# OpenROV_Topside_Interface_2_6.net
KiCad netlist of a schematic drawn in EAGLE
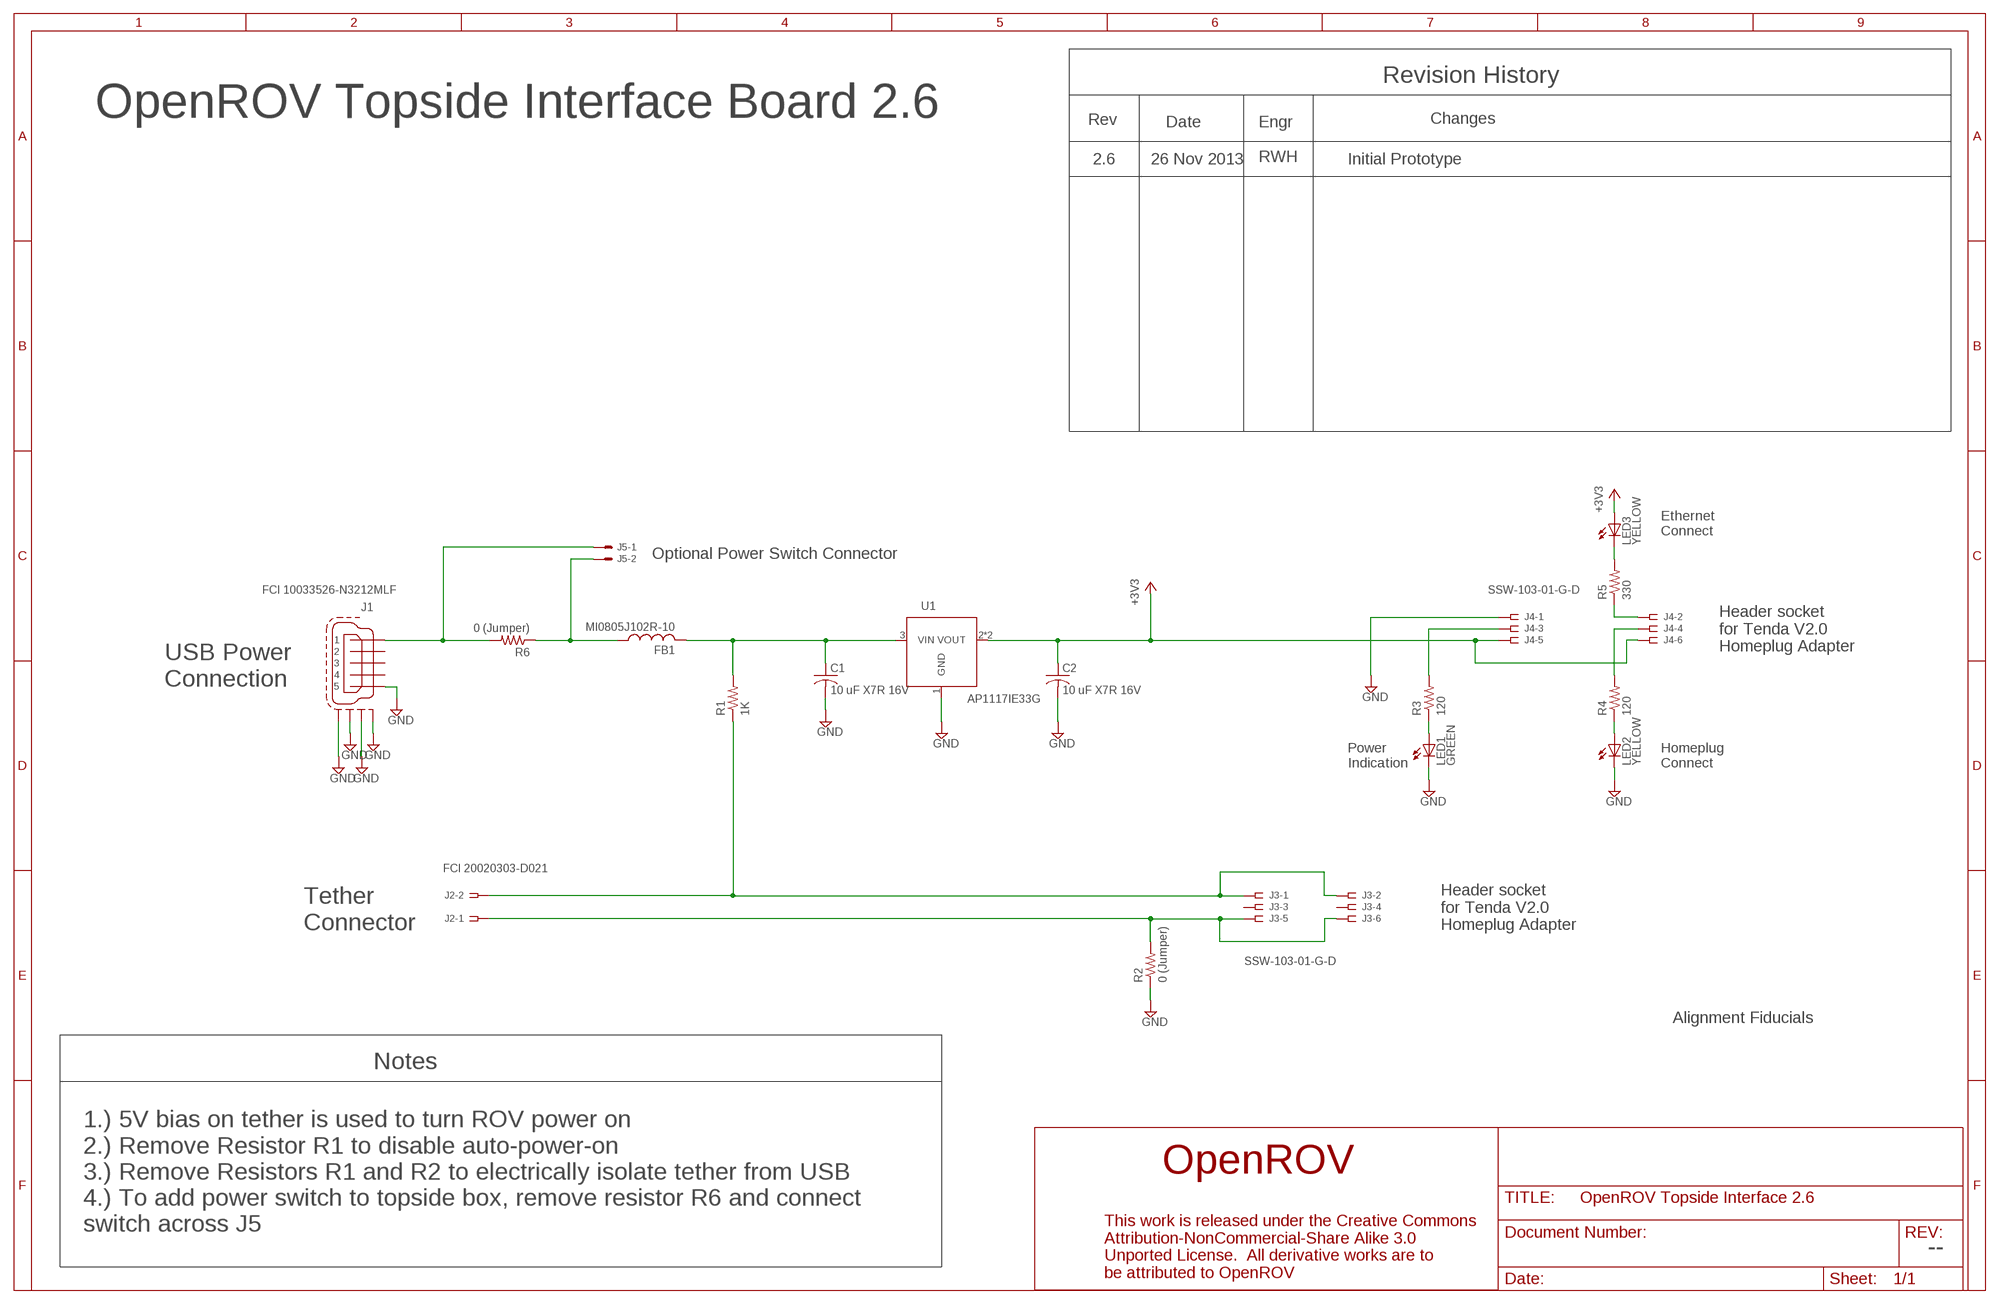
[diagram p0: schematic, sheet 1]

(export (version "E")
  (design (tool "Eeschema 10.0.6"))
  (components
    (comp (ref "C1")
      (value "10 uF X7R 16V")
      (footprint "eagle-import:R1206")
      (libsource (lib "eagle-import") (part "CAP1206"))
    )
    (comp (ref "C2")
      (value "10 uF X7R 16V")
      (footprint "eagle-import:R1206")
      (libsource (lib "eagle-import") (part "CAP1206"))
    )
    (comp (ref "FB1")
      (value "MI0805J102R-10")
      (footprint "eagle-import:R0805")
      (libsource (lib "eagle-import") (part "FERRITESIZE_0805"))
    )
    (comp (ref "J1")
      (value "FCI 10033526-N3212MLF")
      (footprint "eagle-import:USB_MINI-B_SM")
      (libsource (lib "eagle-import") (part "USB_MINI-BSURFACE_MOUNT"))
    )
    (comp (ref "J2")
      (value "FCI 20020303-D021")
      (footprint "eagle-import:FCI_09-381_2PL")
      (libsource (lib "eagle-import") (part "FCI_TERMINAL_BLOCK_2PL"))
    )
    (comp (ref "J3")
      (value "SSW-103-01-G-D")
      (footprint "eagle-import:SSW-103-02-S-D")
      (fields (field (name "MPN") "SSW-103-02-S-D"))
      (libsource (lib "eagle-import") (part "HDR_SOCKET_2X3"))
    )
    (comp (ref "J4")
      (value "SSW-103-01-G-D")
      (footprint "eagle-import:SSW-103-02-S-D")
      (fields (field (name "MPN") "SSW-103-02-S-D"))
      (libsource (lib "eagle-import") (part "HDR_SOCKET_2X3"))
    )
    (comp (ref "J5")
      (value "HDR_1X2X0.100-ALT_SILK")
      (footprint "eagle-import:22-23-2021_ALT_SILK")
      (libsource (lib "eagle-import") (part "HDR_1X2X0.100-ALT_SILK"))
    )
    (comp (ref "LED1")
      (value "GREEN")
      (footprint "eagle-import:LED_0805_BOTTOM_MT(OSRAM)")
      (libsource (lib "eagle-import") (part "LED-0805_BOTTOM_MT"))
    )
    (comp (ref "LED2")
      (value "YELLOW")
      (footprint "eagle-import:LED_0805_BOTTOM_MT(OSRAM)")
      (libsource (lib "eagle-import") (part "LED-0805_BOTTOM_MT"))
    )
    (comp (ref "LED3")
      (value "YELLOW")
      (footprint "eagle-import:LED_0805_BOTTOM_MT(OSRAM)")
      (libsource (lib "eagle-import") (part "LED-0805_BOTTOM_MT"))
    )
    (comp (ref "R1")
      (value "1K")
      (footprint "eagle-import:R0805")
      (libsource (lib "eagle-import") (part "RESISTOR-0805"))
    )
    (comp (ref "R2")
      (value "0 (Jumper)")
      (footprint "eagle-import:R0805")
      (libsource (lib "eagle-import") (part "RESISTOR-0805"))
    )
    (comp (ref "R3")
      (value "120")
      (footprint "eagle-import:R0805")
      (libsource (lib "eagle-import") (part "RESISTOR-0805"))
    )
    (comp (ref "R4")
      (value "120")
      (footprint "eagle-import:R0805")
      (libsource (lib "eagle-import") (part "RESISTOR-0805"))
    )
    (comp (ref "R5")
      (value "330")
      (footprint "eagle-import:R0805")
      (libsource (lib "eagle-import") (part "RESISTOR-0805"))
    )
    (comp (ref "R6")
      (value "0 (Jumper)")
      (footprint "eagle-import:R0805")
      (libsource (lib "eagle-import") (part "RESISTOR-0805"))
    )
    (comp (ref "U1")
      (value "AP1117IE33G")
      (footprint "eagle-import:SOT223")
      (libsource (lib "eagle-import") (part "AP1117SOT223"))
    )
  )
  (nets
    (net (code "1") (name "+3V3") (class "Default")
      (node (ref "C2") (pin "1") (pinfunction "1_1") (pintype "passive"))
      (node (ref "J4") (pin "5") (pinfunction "1_5") (pintype "passive"))
      (node (ref "J4") (pin "6") (pinfunction "1_6") (pintype "passive"))
      (node (ref "LED3") (pin "A") (pinfunction "A_A") (pintype "passive"))
      (node (ref "U1") (pin "2") (pinfunction "VOUT_2") (pintype "bidirectional"))
      (node (ref "U1") (pin "4") (pinfunction "VOUT_4") (pintype "bidirectional"))
    )
    (net (code "2") (name "GND") (class "Default")
      (node (ref "C1") (pin "2") (pinfunction "2_2") (pintype "passive"))
      (node (ref "C2") (pin "2") (pinfunction "2_2") (pintype "passive"))
      (node (ref "J1") (pin "5") (pinfunction "5_5") (pintype "passive"))
      (node (ref "J1") (pin "M1") (pinfunction "S1_M1") (pintype "passive"))
      (node (ref "J1") (pin "M2") (pinfunction "S2_M2") (pintype "passive"))
      (node (ref "J1") (pin "M3") (pinfunction "S3_M3") (pintype "passive"))
      (node (ref "J1") (pin "M4") (pinfunction "S4_M4") (pintype "passive"))
      (node (ref "J4") (pin "1") (pinfunction "1_1") (pintype "passive"))
      (node (ref "LED1") (pin "C") (pinfunction "C_C") (pintype "passive"))
      (node (ref "LED2") (pin "C") (pinfunction "C_C") (pintype "passive"))
      (node (ref "R2") (pin "1") (pinfunction "1_1") (pintype "passive"))
      (node (ref "U1") (pin "1") (pinfunction "GND_1") (pintype "power_in"))
    )
    (net (code "3") (name "Net-(J3B-1)") (class "Default")
      (node (ref "J2") (pin "2A") (pinfunction "1_2A") (pintype "passive"))
      (node (ref "J2") (pin "2B") (pinfunction "1_2B") (pintype "passive"))
      (node (ref "J3") (pin "1") (pinfunction "1_1") (pintype "passive"))
      (node (ref "J3") (pin "2") (pinfunction "1_2") (pintype "passive"))
      (node (ref "R1") (pin "1") (pinfunction "1_1") (pintype "passive"))
    )
    (net (code "4") (name "Net-(J3E-1)") (class "Default")
      (node (ref "J2") (pin "1A") (pinfunction "1_1A") (pintype "passive"))
      (node (ref "J2") (pin "1B") (pinfunction "1_1B") (pintype "passive"))
      (node (ref "J3") (pin "5") (pinfunction "1_5") (pintype "passive"))
      (node (ref "J3") (pin "6") (pinfunction "1_6") (pintype "passive"))
      (node (ref "R2") (pin "2") (pinfunction "2_2") (pintype "passive"))
    )
    (net (code "5") (name "Net-(J4B-1)") (class "Default")
      (node (ref "J4") (pin "2") (pinfunction "1_2") (pintype "passive"))
      (node (ref "R5") (pin "1") (pinfunction "1_1") (pintype "passive"))
    )
    (net (code "6") (name "Net-(J4C-1)") (class "Default")
      (node (ref "J4") (pin "3") (pinfunction "1_3") (pintype "passive"))
      (node (ref "R3") (pin "2") (pinfunction "2_2") (pintype "passive"))
    )
    (net (code "7") (name "Net-(J4D-1)") (class "Default")
      (node (ref "J4") (pin "4") (pinfunction "1_4") (pintype "passive"))
      (node (ref "R4") (pin "2") (pinfunction "2_2") (pintype "passive"))
    )
    (net (code "8") (name "Net-(J5A-S)") (class "Default")
      (node (ref "J1") (pin "1") (pinfunction "1_1") (pintype "passive"))
      (node (ref "J5") (pin "1") (pinfunction "S_1") (pintype "passive"))
      (node (ref "R6") (pin "2") (pinfunction "2_2") (pintype "passive"))
    )
    (net (code "9") (name "Net-(J5B-S)") (class "Default")
      (node (ref "FB1") (pin "1") (pinfunction "1_1") (pintype "passive"))
      (node (ref "J5") (pin "2") (pinfunction "S_2") (pintype "passive"))
      (node (ref "R6") (pin "1") (pinfunction "1_1") (pintype "passive"))
    )
    (net (code "10") (name "Net-(LED1-PadA)") (class "Default")
      (node (ref "LED1") (pin "A") (pinfunction "A_A") (pintype "passive"))
      (node (ref "R3") (pin "1") (pinfunction "1_1") (pintype "passive"))
    )
    (net (code "11") (name "Net-(LED2-PadA)") (class "Default")
      (node (ref "LED2") (pin "A") (pinfunction "A_A") (pintype "passive"))
      (node (ref "R4") (pin "1") (pinfunction "1_1") (pintype "passive"))
    )
    (net (code "12") (name "Net-(LED3-PadC)") (class "Default")
      (node (ref "LED3") (pin "C") (pinfunction "C_C") (pintype "passive"))
      (node (ref "R5") (pin "2") (pinfunction "2_2") (pintype "passive"))
    )
    (net (code "13") (name "Net-(U1-VIN)") (class "Default")
      (node (ref "C1") (pin "1") (pinfunction "1_1") (pintype "passive"))
      (node (ref "FB1") (pin "2") (pinfunction "2_2") (pintype "passive"))
      (node (ref "R1") (pin "2") (pinfunction "2_2") (pintype "passive"))
      (node (ref "U1") (pin "3") (pinfunction "VIN_3") (pintype "input"))
    )
    (net (code "14") (name "unconnected-(J1-Pad2)") (class "Default")
      (node (ref "J1") (pin "2") (pinfunction "2_2") (pintype "passive"))
    )
    (net (code "15") (name "unconnected-(J1-Pad3)") (class "Default")
      (node (ref "J1") (pin "3") (pinfunction "3_3") (pintype "passive"))
    )
    (net (code "16") (name "unconnected-(J1-Pad4)") (class "Default")
      (node (ref "J1") (pin "4") (pinfunction "4_4") (pintype "passive"))
    )
    (net (code "17") (name "unconnected-(J3C-1-Pad3)") (class "Default")
      (node (ref "J3") (pin "3") (pinfunction "1_3") (pintype "passive"))
    )
    (net (code "18") (name "unconnected-(J3D-1-Pad4)") (class "Default")
      (node (ref "J3") (pin "4") (pinfunction "1_4") (pintype "passive"))
    )
  )
)
